# untitled.net
KiCad netlist of a schematic drawn in EAGLE
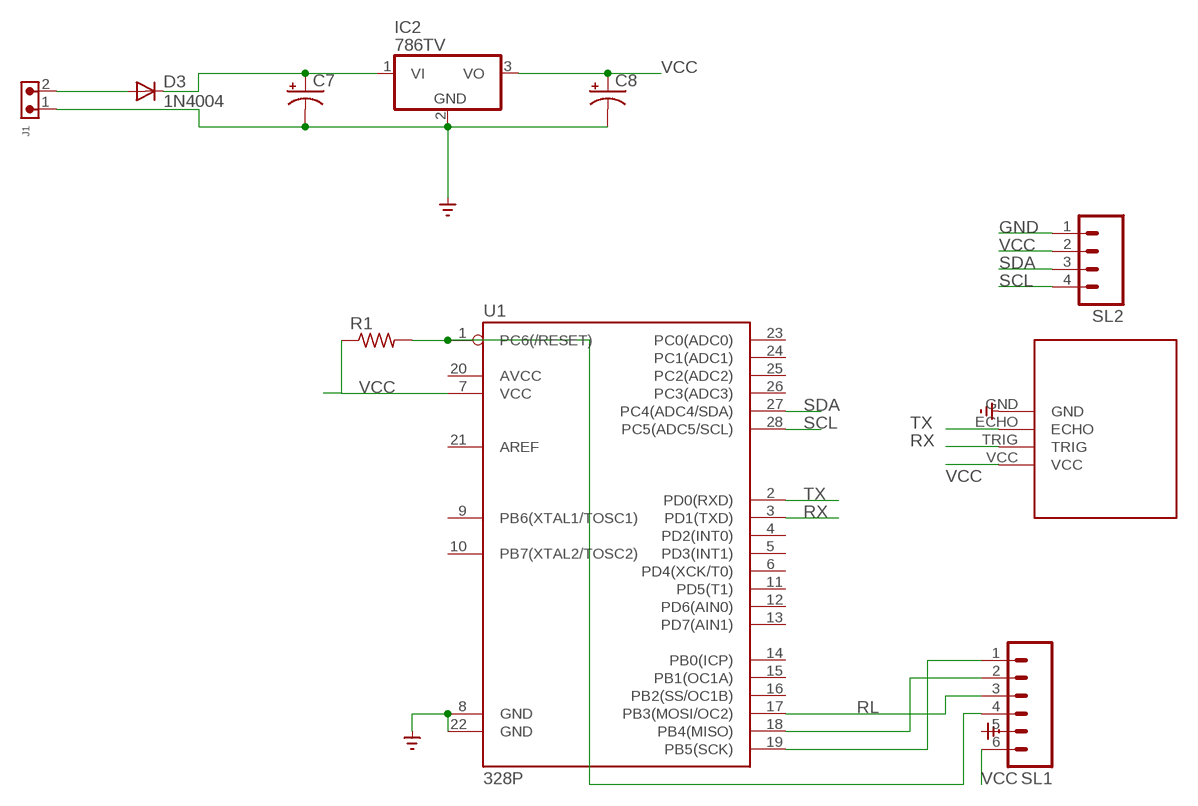
[diagram p0: schematic, sheet 1]

(export (version "E")
  (design (tool "Eeschema 10.0.6"))
  (components
    (comp (ref "C7")
      (value "CAPACITOR-PE5-10.5")
      (footprint "eagle-import:E5-10,5")
      (libsource (lib "eagle-import") (part "CAPACITOR-PE5-10.5"))
    )
    (comp (ref "C8")
      (value "CAPACITOR-PE5-6")
      (footprint "eagle-import:E5-6")
      (libsource (lib "eagle-import") (part "CAPACITOR-PE5-6"))
    )
    (comp (ref "D3")
      (value "1N4004")
      (footprint "eagle-import:DO41-10")
      (libsource (lib "eagle-import") (part "1N4004"))
    )
    (comp (ref "IC2")
      (value "786TV")
      (footprint "eagle-import:TO220V")
      (libsource (lib "eagle-import") (part "78TV6"))
    )
    (comp (ref "J1")
      (value "691305530002")
      (footprint "eagle-import:691305530002")
      (libsource (lib "eagle-import") (part "691305530002"))
    )
    (comp (ref "R1")
      (value "R-US_0207/7")
      (footprint "eagle-import:0207_7")
      (libsource (lib "eagle-import") (part "R-US_0207/7"))
    )
    (comp (ref "SL1")
      (value "M06")
      (footprint "eagle-import:06P")
      (libsource (lib "eagle-import") (part "M06"))
    )
    (comp (ref "SL2")
      (value "M04")
      (footprint "eagle-import:04P")
      (libsource (lib "eagle-import") (part "M04"))
    )
    (comp (ref "U$6")
      (value "SRO4M")
      (footprint "eagle-import:SRO4M")
      (libsource (lib "eagle-import") (part "SRO4M"))
    )
    (comp (ref "U1")
      (value "328P")
      (footprint "eagle-import:DIP28")
      (libsource (lib "eagle-import") (part "ATMEGA328P_PDIP"))
    )
  )
  (nets
    (net (code "1") (name "/RL") (class "Default")
      (node (ref "SL1") (pin "3") (pinfunction "3_3") (pintype "passive"))
      (node (ref "U1") (pin "17") (pinfunction "PB3(MOSI/OC2)_17") (pintype "bidirectional"))
    )
    (net (code "2") (name "/RX") (class "Default")
      (node (ref "U$6") (pin "TRIG") (pinfunction "TRIG_TRIG") (pintype "bidirectional"))
      (node (ref "U1") (pin "3") (pinfunction "PD1(TXD)_3") (pintype "bidirectional"))
    )
    (net (code "3") (name "/SCL") (class "Default")
      (node (ref "SL2") (pin "4") (pinfunction "4_4") (pintype "passive"))
      (node (ref "U1") (pin "28") (pinfunction "PC5(ADC5/SCL)_28") (pintype "bidirectional"))
    )
    (net (code "4") (name "/SDA") (class "Default")
      (node (ref "SL2") (pin "3") (pinfunction "3_3") (pintype "passive"))
      (node (ref "U1") (pin "27") (pinfunction "PC4(ADC4/SDA)_27") (pintype "bidirectional"))
    )
    (net (code "5") (name "/TX") (class "Default")
      (node (ref "U$6") (pin "ECHO") (pinfunction "ECHO_ECHO") (pintype "bidirectional"))
      (node (ref "U1") (pin "2") (pinfunction "PD0(RXD)_2") (pintype "bidirectional"))
    )
    (net (code "6") (name "/VCC") (class "Default")
      (node (ref "C8") (pin "+") (pinfunction "+_+") (pintype "passive"))
      (node (ref "IC2") (pin "3") (pinfunction "VO_3") (pintype "passive"))
      (node (ref "R1") (pin "1") (pinfunction "1_1") (pintype "passive"))
      (node (ref "SL1") (pin "6") (pinfunction "6_6") (pintype "passive"))
      (node (ref "SL2") (pin "2") (pinfunction "2_2") (pintype "passive"))
      (node (ref "U$6") (pin "VCC") (pinfunction "VCC_VCC") (pintype "bidirectional"))
      (node (ref "U1") (pin "7") (pinfunction "VCC_7") (pintype "bidirectional"))
    )
    (net (code "7") (name "Net-(D3-PadA)") (class "Default")
      (node (ref "D3") (pin "A") (pinfunction "A_A") (pintype "passive"))
      (node (ref "J1") (pin "2") (pinfunction "2_2") (pintype "passive"))
    )
    (net (code "8") (name "Net-(IC2-VI)") (class "Default")
      (node (ref "C7") (pin "+") (pinfunction "+_+") (pintype "passive"))
      (node (ref "D3") (pin "C") (pinfunction "C_C") (pintype "passive"))
      (node (ref "IC2") (pin "1") (pinfunction "VI_1") (pintype "input"))
    )
    (net (code "9") (name "Net-(U1-PB4(MISO))") (class "Default")
      (node (ref "SL1") (pin "2") (pinfunction "2_2") (pintype "passive"))
      (node (ref "U1") (pin "18") (pinfunction "PB4(MISO)_18") (pintype "bidirectional"))
    )
    (net (code "10") (name "Net-(U1-PB5(SCK))") (class "Default")
      (node (ref "SL1") (pin "1") (pinfunction "1_1") (pintype "passive"))
      (node (ref "U1") (pin "19") (pinfunction "PB5(SCK)_19") (pintype "bidirectional"))
    )
    (net (code "11") (name "Net-(U1-PC6({slash}RESET))") (class "Default")
      (node (ref "R1") (pin "2") (pinfunction "2_2") (pintype "passive"))
      (node (ref "SL1") (pin "4") (pinfunction "4_4") (pintype "passive"))
      (node (ref "U1") (pin "1") (pinfunction "PC6(/RESET)_1") (pintype "bidirectional"))
    )
    (net (code "12") (name "SUPPLY_BRASTAN_GND_") (class "Default")
      (node (ref "C7") (pin "-") (pinfunction "-_-") (pintype "passive"))
      (node (ref "C8") (pin "-") (pinfunction "-_-") (pintype "passive"))
      (node (ref "IC2") (pin "2") (pinfunction "GND_2") (pintype "passive"))
      (node (ref "J1") (pin "1") (pinfunction "1_1") (pintype "passive"))
      (node (ref "SL1") (pin "5") (pinfunction "5_5") (pintype "passive"))
      (node (ref "SL2") (pin "1") (pinfunction "1_1") (pintype "passive"))
      (node (ref "U$6") (pin "GND") (pinfunction "GND_GND") (pintype "bidirectional"))
      (node (ref "U1") (pin "22") (pinfunction "GND_22") (pintype "bidirectional"))
      (node (ref "U1") (pin "8") (pinfunction "GND_8") (pintype "bidirectional"))
    )
    (net (code "13") (name "unconnected-(U1-AREF-Pad21)") (class "Default")
      (node (ref "U1") (pin "21") (pinfunction "AREF_21") (pintype "bidirectional"))
    )
    (net (code "14") (name "unconnected-(U1-AVCC-Pad20)") (class "Default")
      (node (ref "U1") (pin "20") (pinfunction "AVCC_20") (pintype "bidirectional"))
    )
    (net (code "15") (name "unconnected-(U1-PB0(ICP)-Pad14)") (class "Default")
      (node (ref "U1") (pin "14") (pinfunction "PB0(ICP)_14") (pintype "bidirectional"))
    )
    (net (code "16") (name "unconnected-(U1-PB1(OC1A)-Pad15)") (class "Default")
      (node (ref "U1") (pin "15") (pinfunction "PB1(OC1A)_15") (pintype "bidirectional"))
    )
    (net (code "17") (name "unconnected-(U1-PB2(SS{slash}OC1B)-Pad16)") (class "Default")
      (node (ref "U1") (pin "16") (pinfunction "PB2(SS/OC1B)_16") (pintype "bidirectional"))
    )
    (net (code "18") (name "unconnected-(U1-PB6(XTAL1{slash}TOSC1)-Pad9)") (class "Default")
      (node (ref "U1") (pin "9") (pinfunction "PB6(XTAL1/TOSC1)_9") (pintype "bidirectional"))
    )
    (net (code "19") (name "unconnected-(U1-PB7(XTAL2{slash}TOSC2)-Pad10)") (class "Default")
      (node (ref "U1") (pin "10") (pinfunction "PB7(XTAL2/TOSC2)_10") (pintype "bidirectional"))
    )
    (net (code "20") (name "unconnected-(U1-PC0(ADC0)-Pad23)") (class "Default")
      (node (ref "U1") (pin "23") (pinfunction "PC0(ADC0)_23") (pintype "bidirectional"))
    )
    (net (code "21") (name "unconnected-(U1-PC1(ADC1)-Pad24)") (class "Default")
      (node (ref "U1") (pin "24") (pinfunction "PC1(ADC1)_24") (pintype "bidirectional"))
    )
    (net (code "22") (name "unconnected-(U1-PC2(ADC2)-Pad25)") (class "Default")
      (node (ref "U1") (pin "25") (pinfunction "PC2(ADC2)_25") (pintype "bidirectional"))
    )
    (net (code "23") (name "unconnected-(U1-PC3(ADC3)-Pad26)") (class "Default")
      (node (ref "U1") (pin "26") (pinfunction "PC3(ADC3)_26") (pintype "bidirectional"))
    )
    (net (code "24") (name "unconnected-(U1-PD2(INT0)-Pad4)") (class "Default")
      (node (ref "U1") (pin "4") (pinfunction "PD2(INT0)_4") (pintype "bidirectional"))
    )
    (net (code "25") (name "unconnected-(U1-PD3(INT1)-Pad5)") (class "Default")
      (node (ref "U1") (pin "5") (pinfunction "PD3(INT1)_5") (pintype "bidirectional"))
    )
    (net (code "26") (name "unconnected-(U1-PD4(XCK{slash}T0)-Pad6)") (class "Default")
      (node (ref "U1") (pin "6") (pinfunction "PD4(XCK/T0)_6") (pintype "bidirectional"))
    )
    (net (code "27") (name "unconnected-(U1-PD5(T1)-Pad11)") (class "Default")
      (node (ref "U1") (pin "11") (pinfunction "PD5(T1)_11") (pintype "bidirectional"))
    )
    (net (code "28") (name "unconnected-(U1-PD6(AIN0)-Pad12)") (class "Default")
      (node (ref "U1") (pin "12") (pinfunction "PD6(AIN0)_12") (pintype "bidirectional"))
    )
    (net (code "29") (name "unconnected-(U1-PD7(AIN1)-Pad13)") (class "Default")
      (node (ref "U1") (pin "13") (pinfunction "PD7(AIN1)_13") (pintype "bidirectional"))
    )
  )
)
